# STLink_V3E_Module.net
KiCad netlist of a schematic drawn in Altium Designer
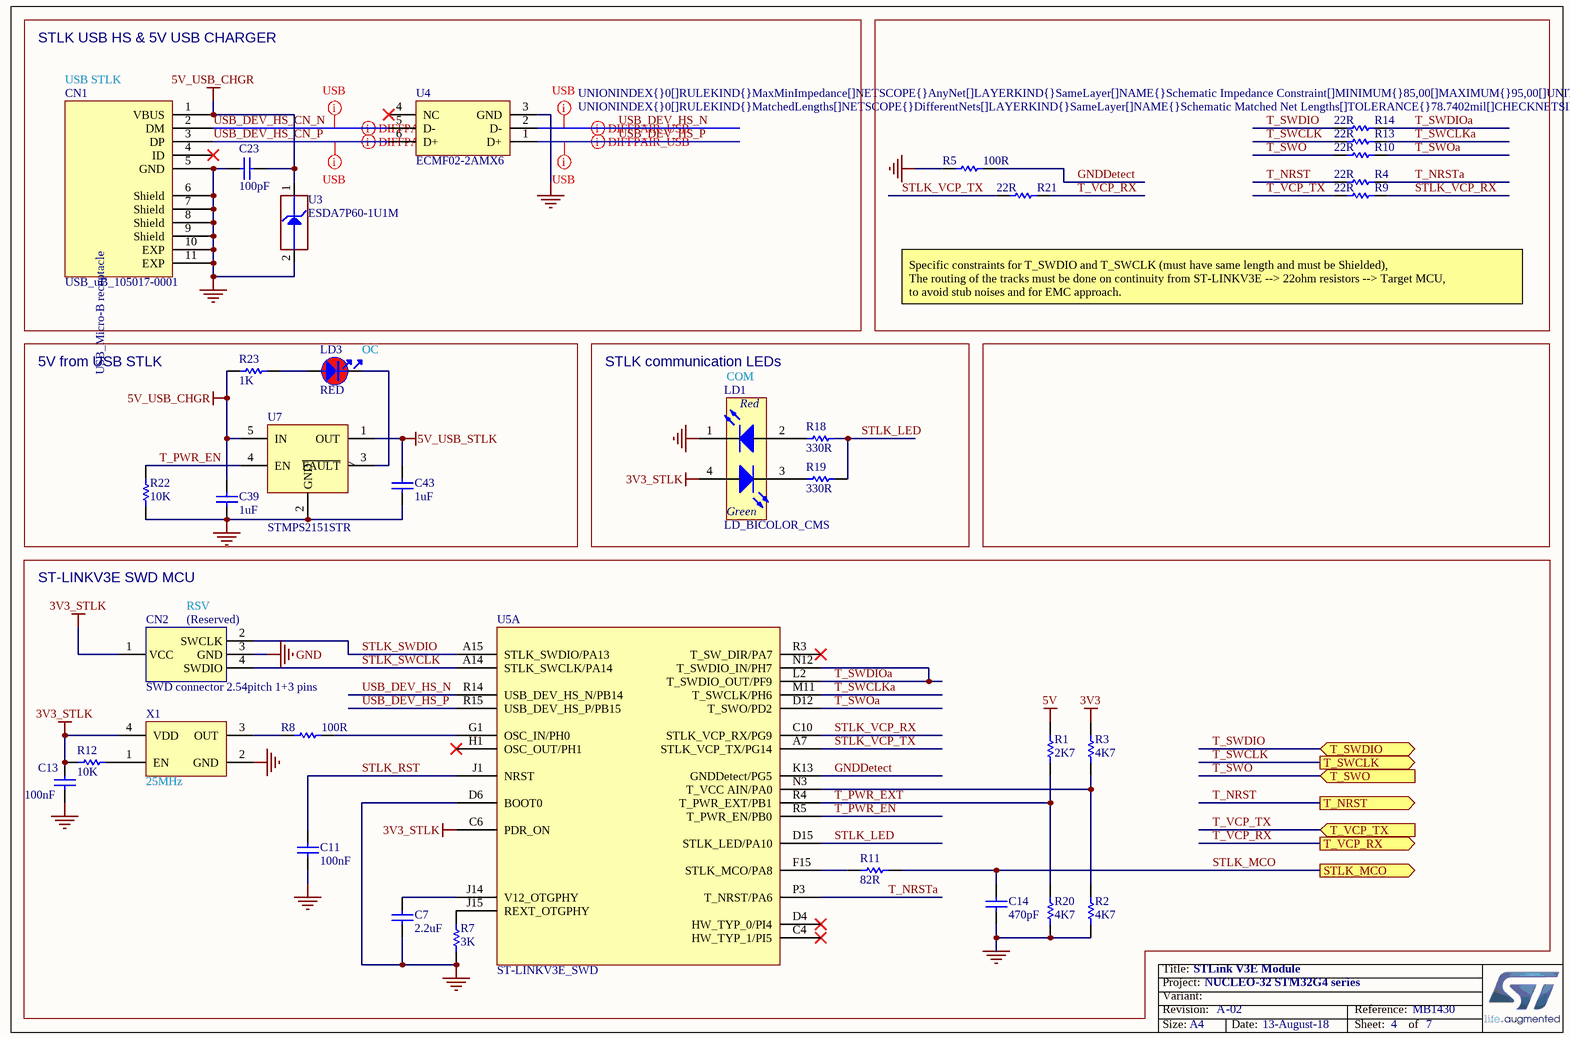
[diagram p0: STLink_V3E_Module.SchDoc]

(export (version "E")
  (design (tool "Eeschema 10.0.6"))
  (components
    (comp (ref "C7")
      (value "2.2uF")
      (footprint "C0603")
      (description "Capacitor, MLCC, 2.2uF, 10V, X5R, 10%, 0603, T=0,8mm")
      (fields
        (field (name "INTERNAL_PART_NUMBER") "MCD-00012")
        (field (name "MANUFACTURER_PART_NUMBER") "CC0603KRX5R6BB225")
        (field (name "PROVIDED_BY") "SUBCO")
      )
      (libsource (lib "MCD_PARTS_database") (part "Capacitor"))
    )
    (comp (ref "C11")
      (value "100nF")
      (footprint "C0402")
      (description "Capacitor, MLCC, 100nF, 16V, X7R, 10%, 0402, T=0,5mm")
      (fields
        (field (name "INTERNAL_PART_NUMBER") "MCD-00102")
        (field (name "MANUFACTURER_PART_NUMBER") "CC0402KRX7R7BB104")
        (field (name "PROVIDED_BY") "SUBCO")
      )
      (libsource (lib "MCD_PARTS_database") (part "Capacitor"))
    )
    (comp (ref "C13")
      (value "100nF")
      (footprint "C0402")
      (description "Capacitor, MLCC, 100nF, 16V, X7R, 10%, 0402, T=0,5mm")
      (fields
        (field (name "INTERNAL_PART_NUMBER") "MCD-00102")
        (field (name "MANUFACTURER_PART_NUMBER") "CC0402KRX7R7BB104")
        (field (name "PROVIDED_BY") "SUBCO")
      )
      (libsource (lib "MCD_PARTS_database") (part "Capacitor"))
    )
    (comp (ref "C14")
      (value "470pF")
      (footprint "C0402")
      (description "Capacitor, MLCC, 470pF, 50V, NPO, 5%, 0402, T=0,5mm")
      (fields
        (field (name "INTERNAL_PART_NUMBER") "MCD-00724")
        (field (name "MANUFACTURER_PART_NUMBER") "CC0402JRNPO9BN471")
        (field (name "PROVIDED_BY") "SUBCO")
      )
      (libsource (lib "MCD_PARTS_database") (part "Capacitor"))
    )
    (comp (ref "C23")
      (value "100pF")
      (footprint "C0402")
      (description "Capacitor, MLCC, 100pF, 50V, NPO, 5%, 0402, T=0,5mm")
      (fields
        (field (name "INTERNAL_PART_NUMBER") "MCD-00205")
        (field (name "MANUFACTURER_PART_NUMBER") "CC0402JRNPO9BN101")
        (field (name "PROVIDED_BY") "SUBCO")
      )
      (libsource (lib "MCD_PARTS_database") (part "Capacitor"))
    )
    (comp (ref "C39")
      (value "1uF")
      (footprint "C0603")
      (description "Capacitor, MLCC, 1uF, 16V, X5R, 10%, 0603, T=0,8mm")
      (fields
        (field (name "INTERNAL_PART_NUMBER") "MCD-00010")
        (field (name "MANUFACTURER_PART_NUMBER") "CC0603KRX5R7BB105")
        (field (name "PROVIDED_BY") "SUBCO")
      )
      (libsource (lib "MCD_PARTS_database") (part "Capacitor"))
    )
    (comp (ref "C43")
      (value "1uF")
      (footprint "C0603")
      (description "Capacitor, MLCC, 1uF, 16V, X5R, 10%, 0603, T=0,8mm")
      (fields
        (field (name "INTERNAL_PART_NUMBER") "MCD-00010")
        (field (name "MANUFACTURER_PART_NUMBER") "CC0603KRX5R7BB105")
        (field (name "PROVIDED_BY") "SUBCO")
      )
      (libsource (lib "MCD_PARTS_database") (part "Capacitor"))
    )
    (comp (ref "CN1")
      (value "USB_uB_105017-0001")
      (footprint "CON_USBMICROB_MOLEX_105017-0001_H2P90")
      (description "USB-MICRO-B, 0.65mm, RA, SMT, Bottom Mount,")
      (fields
        (field (name "INTERNAL_PART_NUMBER") "MCD-00028")
        (field (name "MANUFACTURER_PART_NUMBER") "1050170001")
        (field (name "PROVIDED_BY") "SUBCO")
      )
      (libsource (lib "MCD_PARTS_database") (part "USB_uB_105017.0001"))
    )
    (comp (ref "CN2")
      (value "SWD connector 2.54pitch 1+3 pins")
      (footprint "CON_SAMTEC_TSW-103-07-X-D_CUSTOM_4PINS__V1-3")
      (description "SWD connector 2.54pitch 1+3 pins - not fitted")
      (fields
        (field (name "INTERNAL_PART_NUMBER") "MCD-01430")
        (field (name "MANUFACTURER_PART_NUMBER") "na")
      )
      (libsource (lib "MCD_PARTS_database") (part "SWD_CN_1+3"))
    )
    (comp (ref "LD1")
      (value "LD_BICOLOR_CMS")
      (footprint "LED_BI-GR_HSMF-A201-A00J1")
      (description "LED Bicolor")
      (fields
        (field (name "INTERNAL_PART_NUMBER") "MCD-00051")
        (field (name "MANUFACTURER_PART_NUMBER") "HSMF-A201-A00J1")
        (field (name "PROVIDED_BY") "SUBCO")
      )
      (libsource (lib "MCD_PARTS_database") (part "LD_BICOLOR_CMS"))
    )
    (comp (ref "LD3")
      (value "RED")
      (footprint "LED_0603_RED_H0P4")
      (description "LED, Red, 0603")
      (fields
        (field (name "INTERNAL_PART_NUMBER") "MCD-00322")
        (field (name "MANUFACTURER_PART_NUMBER") "19-217/R6C-AL1M2VY/3T")
        (field (name "PROVIDED_BY") "SUBCO")
      )
      (libsource (lib "MCD_PARTS_database") (part "LED_red"))
    )
    (comp (ref "R1")
      (value "2K7")
      (footprint "R0402")
      (description "Resistor,2K7,0402,1%,1/16W")
      (fields
        (field (name "INTERNAL_PART_NUMBER") "MCD-00055")
        (field (name "MANUFACTURER_PART_NUMBER") "RC0402FR-072K7L")
        (field (name "PROVIDED_BY") "SUBCO")
      )
      (libsource (lib "MCD_PARTS_database") (part "Resistor"))
    )
    (comp (ref "R2")
      (value "4K7")
      (footprint "R0402")
      (description "Resistor,4K7,0402,1%,1/16W")
      (fields
        (field (name "INTERNAL_PART_NUMBER") "MCD-00065")
        (field (name "MANUFACTURER_PART_NUMBER") "RC0402FR-074K7L")
        (field (name "PROVIDED_BY") "SUBCO")
      )
      (libsource (lib "MCD_PARTS_database") (part "Resistor"))
    )
    (comp (ref "R3")
      (value "4K7")
      (footprint "R0402")
      (description "Resistor,4K7,0402,1%,1/16W")
      (fields
        (field (name "INTERNAL_PART_NUMBER") "MCD-00065")
        (field (name "MANUFACTURER_PART_NUMBER") "RC0402FR-074K7L")
        (field (name "PROVIDED_BY") "SUBCO")
      )
      (libsource (lib "MCD_PARTS_database") (part "Resistor"))
    )
    (comp (ref "R4")
      (value "22R")
      (footprint "R0402")
      (description "Resistor,22R,0402,1%,1/16W")
      (fields
        (field (name "INTERNAL_PART_NUMBER") "MCD-00189")
        (field (name "MANUFACTURER_PART_NUMBER") "RC0402FR-0722RL")
        (field (name "PROVIDED_BY") "SUBCO")
      )
      (libsource (lib "MCD_PARTS_database") (part "Resistor"))
    )
    (comp (ref "R5")
      (value "100R")
      (footprint "R0402")
      (description "Resistor,100R,0402,1%,1/16W")
      (fields
        (field (name "INTERNAL_PART_NUMBER") "MCD-00119")
        (field (name "MANUFACTURER_PART_NUMBER") "RC0402FR-07100RL")
        (field (name "PROVIDED_BY") "SUBCO")
      )
      (libsource (lib "MCD_PARTS_database") (part "Resistor"))
    )
    (comp (ref "R7")
      (value "3K")
      (footprint "R0402")
      (description "Resistor,3K,0402,1%,1/16W")
      (fields
        (field (name "INTERNAL_PART_NUMBER") "MCD-00185")
        (field (name "MANUFACTURER_PART_NUMBER") "RC0402FR-073KL")
        (field (name "PROVIDED_BY") "SUBCO")
      )
      (libsource (lib "MCD_PARTS_database") (part "Resistor"))
    )
    (comp (ref "R8")
      (value "100R")
      (footprint "R0402")
      (description "Resistor,100R,0402,1%,1/16W")
      (fields
        (field (name "INTERNAL_PART_NUMBER") "MCD-00119")
        (field (name "MANUFACTURER_PART_NUMBER") "RC0402FR-07100RL")
        (field (name "PROVIDED_BY") "SUBCO")
      )
      (libsource (lib "MCD_PARTS_database") (part "Resistor"))
    )
    (comp (ref "R9")
      (value "22R")
      (footprint "R0402")
      (description "Resistor,22R,0402,1%,1/16W")
      (fields
        (field (name "INTERNAL_PART_NUMBER") "MCD-00189")
        (field (name "MANUFACTURER_PART_NUMBER") "RC0402FR-0722RL")
        (field (name "PROVIDED_BY") "SUBCO")
      )
      (libsource (lib "MCD_PARTS_database") (part "Resistor"))
    )
    (comp (ref "R10")
      (value "22R")
      (footprint "R0402")
      (description "Resistor,22R,0402,1%,1/16W")
      (fields
        (field (name "INTERNAL_PART_NUMBER") "MCD-00189")
        (field (name "MANUFACTURER_PART_NUMBER") "RC0402FR-0722RL")
        (field (name "PROVIDED_BY") "SUBCO")
      )
      (libsource (lib "MCD_PARTS_database") (part "Resistor"))
    )
    (comp (ref "R11")
      (value "82R")
      (footprint "R0402")
      (description "Resistor,82R,0402,1%,1/16W")
      (fields
        (field (name "INTERNAL_PART_NUMBER") "MCD-00525")
        (field (name "MANUFACTURER_PART_NUMBER") "RC0402FR-0782RL")
        (field (name "PROVIDED_BY") "SUBCO")
      )
      (libsource (lib "MCD_PARTS_database") (part "Resistor"))
    )
    (comp (ref "R12")
      (value "10K")
      (footprint "R0402")
      (description "Resistor,10K,0402,1%,1/16W")
      (fields
        (field (name "INTERNAL_PART_NUMBER") "MCD-00053")
        (field (name "MANUFACTURER_PART_NUMBER") "RC0402FR-0710KL")
        (field (name "PROVIDED_BY") "SUBCO")
      )
      (libsource (lib "MCD_PARTS_database") (part "Resistor"))
    )
    (comp (ref "R13")
      (value "22R")
      (footprint "R0402")
      (description "Resistor,22R,0402,1%,1/16W")
      (fields
        (field (name "INTERNAL_PART_NUMBER") "MCD-00189")
        (field (name "MANUFACTURER_PART_NUMBER") "RC0402FR-0722RL")
        (field (name "PROVIDED_BY") "SUBCO")
      )
      (libsource (lib "MCD_PARTS_database") (part "Resistor"))
    )
    (comp (ref "R14")
      (value "22R")
      (footprint "R0402")
      (description "Resistor,22R,0402,1%,1/16W")
      (fields
        (field (name "INTERNAL_PART_NUMBER") "MCD-00189")
        (field (name "MANUFACTURER_PART_NUMBER") "RC0402FR-0722RL")
        (field (name "PROVIDED_BY") "SUBCO")
      )
      (libsource (lib "MCD_PARTS_database") (part "Resistor"))
    )
    (comp (ref "R18")
      (value "330R")
      (footprint "R0603")
      (description "Resistor,330R,0603,1%,1/10W")
      (fields
        (field (name "INTERNAL_PART_NUMBER") "MCD-00197")
        (field (name "MANUFACTURER_PART_NUMBER") "RC0603FR-07330RL")
        (field (name "PROVIDED_BY") "SUBCO")
      )
      (libsource (lib "MCD_PARTS_database") (part "Resistor"))
    )
    (comp (ref "R19")
      (value "330R")
      (footprint "R0603")
      (description "Resistor,330R,0603,1%,1/10W")
      (fields
        (field (name "INTERNAL_PART_NUMBER") "MCD-00197")
        (field (name "MANUFACTURER_PART_NUMBER") "RC0603FR-07330RL")
        (field (name "PROVIDED_BY") "SUBCO")
      )
      (libsource (lib "MCD_PARTS_database") (part "Resistor"))
    )
    (comp (ref "R20")
      (value "4K7")
      (footprint "R0402")
      (description "Resistor,4K7,0402,1%,1/16W")
      (fields
        (field (name "INTERNAL_PART_NUMBER") "MCD-00065")
        (field (name "MANUFACTURER_PART_NUMBER") "RC0402FR-074K7L")
        (field (name "PROVIDED_BY") "SUBCO")
      )
      (libsource (lib "MCD_PARTS_database") (part "Resistor"))
    )
    (comp (ref "R21")
      (value "22R")
      (footprint "R0402")
      (description "Resistor,22R,0402,1%,1/16W")
      (fields
        (field (name "INTERNAL_PART_NUMBER") "MCD-00189")
        (field (name "MANUFACTURER_PART_NUMBER") "RC0402FR-0722RL")
        (field (name "PROVIDED_BY") "SUBCO")
      )
      (libsource (lib "MCD_PARTS_database") (part "Resistor"))
    )
    (comp (ref "R22")
      (value "10K")
      (footprint "R0402")
      (description "Resistor,10K,0402,1%,1/16W")
      (fields
        (field (name "INTERNAL_PART_NUMBER") "MCD-00053")
        (field (name "MANUFACTURER_PART_NUMBER") "RC0402FR-0710KL")
        (field (name "PROVIDED_BY") "SUBCO")
      )
      (libsource (lib "MCD_PARTS_database") (part "Resistor"))
    )
    (comp (ref "R23")
      (value "1K")
      (footprint "R0603")
      (description "Resistor,1K,0603,1%,1/10W")
      (fields
        (field (name "INTERNAL_PART_NUMBER") "MCD-00070")
        (field (name "MANUFACTURER_PART_NUMBER") "RC0603FR-071KL")
        (field (name "PROVIDED_BY") "SUBCO")
      )
      (libsource (lib "MCD_PARTS_database") (part "Resistor"))
    )
    (comp (ref "U3")
      (value "ESDA7P60-1U1M")
      (footprint "ESD_QFN2_1P6X1_P125")
      (description "High power transient voltage suppressor, 7V breakdown")
      (fields
        (field (name "INTERNAL_PART_NUMBER") "MCD-00251")
        (field (name "MANUFACTURER") "STMICROELECTRONICS")
        (field (name "PROVIDED_BY") "SUBCO with ST control")
      )
      (libsource (lib "MCD_PARTS_database") (part "ESD-TRANSIL"))
    )
    (comp (ref "U4")
      (value "ECMF02-2AMX6")
      (footprint "ESD_QFN-6L_1P7X1P5_P050")
      (description "Common mode filter with ESD protection for USB 2.0 interface")
      (fields
        (field (name "INTERNAL_PART_NUMBER") "MCD-00649")
        (field (name "MANUFACTURER") "STMICROELECTRONICS")
        (field (name "PROVIDED_BY") "SUBCO with ST control")
      )
      (libsource (lib "MCD_PARTS_database") (part "ECMF02-2AMX6"))
    )
    (comp (ref "U5")
      (value "ST-LINKV3E_SWD")
      (footprint "ICC_UFBGA201_176+25_10X10_P065")
      (description "STM32F723IEK  (STM32F7) BGA176")
      (fields
        (field (name "INTERNAL_PART_NUMBER") "MCD-00596")
        (field (name "MANUFACTURER_PART_NUMBER") "STM32F723IEK6")
        (field (name "PROVIDED_BY") "SUBCO with ST control")
      )
      (libsource (lib "MCD_PARTS_database") (part "ST-LINKV3E_SWD"))
    )
    (comp (ref "U7")
      (value "STMPS2151STR")
      (footprint "MOS_SOT23-5L")
      (description "500mA, Enhanced single channel power switches with active high enable pin")
      (fields
        (field (name "INTERNAL_PART_NUMBER") "MCD-00159")
        (field (name "MANUFACTURER") "STMICROELECTRONICS")
        (field (name "PROVIDED_BY") "SUBCO with ST control")
      )
      (libsource (lib "MCD_PARTS_database") (part "STMPS2151STR"))
    )
    (comp (ref "X1")
      (value "25MHz")
      (footprint "OSC_NDK_NZ2520SB_4P")
      (description "Oscillator 25.00Mhz, -+50PPM, 3.3V, Temp -55 to +125°C")
      (fields
        (field (name "INTERNAL_PART_NUMBER") "MCD-00597")
        (field (name "MANUFACTURER_PART_NUMBER") "NZ2520SB 25MHz END4869B")
      )
      (libsource (lib "MCD_PARTS_database") (part "OSCILLATOR_4_PINS"))
    )
  )
  (nets
    (net (code "1") (name "/GNDDetect") (class "Default")
      (node (ref "R5") (pin "2") (pinfunction "2_2") (pintype "passive"))
      (node (ref "U5") (pin "K13") (pinfunction "GNDDetect/PG5_K13") (pintype "passive"))
    )
    (net (code "2") (name "/STLK_LED") (class "Default")
      (node (ref "R18") (pin "2") (pinfunction "2_2") (pintype "passive"))
      (node (ref "R19") (pin "2") (pinfunction "2_2") (pintype "passive"))
      (node (ref "U5") (pin "D15") (pinfunction "STLK_LED/PA10_D15") (pintype "passive"))
    )
    (net (code "3") (name "/STLK_MCO") (class "Default")
      (node (ref "C14") (pin "2") (pinfunction "2_2") (pintype "passive"))
      (node (ref "R11") (pin "2") (pinfunction "2_2") (pintype "passive"))
    )
    (net (code "4") (name "/STLK_RST") (class "Default")
      (node (ref "C11") (pin "2") (pinfunction "2_2") (pintype "passive"))
      (node (ref "U5") (pin "J1") (pinfunction "NRST_J1") (pintype "passive"))
    )
    (net (code "5") (name "/STLK_SWCLK") (class "Default")
      (node (ref "CN2") (pin "4") (pinfunction "SWDIO_4") (pintype "passive"))
      (node (ref "U5") (pin "A14") (pinfunction "STLK_SWCLK/PA14_A14") (pintype "passive"))
    )
    (net (code "6") (name "/STLK_SWDIO") (class "Default")
      (node (ref "CN2") (pin "2") (pinfunction "SWCLK_2") (pintype "passive"))
      (node (ref "U5") (pin "A15") (pinfunction "STLK_SWDIO/PA13_A15") (pintype "passive"))
    )
    (net (code "7") (name "/STLK_VCP_RX") (class "Default")
      (node (ref "R9") (pin "2") (pinfunction "2_2") (pintype "passive"))
      (node (ref "U5") (pin "C10") (pinfunction "STLK_VCP_RX/PG9_C10") (pintype "passive"))
    )
    (net (code "8") (name "/STLK_VCP_TX") (class "Default")
      (node (ref "R21") (pin "1") (pinfunction "1_1") (pintype "passive"))
      (node (ref "U5") (pin "A7") (pinfunction "STLK_VCP_TX/PG14_A7") (pintype "passive"))
    )
    (net (code "9") (name "/T_NRST") (class "Default")
      (node (ref "R4") (pin "1") (pinfunction "1_1") (pintype "passive"))
    )
    (net (code "10") (name "/T_NRSTa") (class "Default")
      (node (ref "R4") (pin "2") (pinfunction "2_2") (pintype "passive"))
      (node (ref "U5") (pin "P3") (pinfunction "T_NRST/PA6_P3") (pintype "passive"))
    )
    (net (code "11") (name "/T_PWR_EN") (class "Default")
      (node (ref "R22") (pin "2") (pinfunction "2_2") (pintype "passive"))
      (node (ref "U5") (pin "R5") (pinfunction "T_PWR_EN/PB0_R5") (pintype "passive"))
      (node (ref "U7") (pin "4") (pinfunction "EN_4") (pintype "passive"))
    )
    (net (code "12") (name "/T_PWR_EXT") (class "Default")
      (node (ref "R1") (pin "1") (pinfunction "1_1") (pintype "passive"))
      (node (ref "R20") (pin "2") (pinfunction "2_2") (pintype "passive"))
      (node (ref "U5") (pin "R4") (pinfunction "T_PWR_EXT/PB1_R4") (pintype "passive"))
    )
    (net (code "13") (name "/T_SWCLK") (class "Default")
      (node (ref "R13") (pin "1") (pinfunction "1_1") (pintype "passive"))
    )
    (net (code "14") (name "/T_SWCLKa") (class "Default")
      (node (ref "R13") (pin "2") (pinfunction "2_2") (pintype "passive"))
      (node (ref "U5") (pin "M11") (pinfunction "T_SWCLK/PH6_M11") (pintype "passive"))
    )
    (net (code "15") (name "/T_SWDIO") (class "Default")
      (node (ref "R14") (pin "1") (pinfunction "1_1") (pintype "passive"))
    )
    (net (code "16") (name "/T_SWDIOa") (class "Default")
      (node (ref "R14") (pin "2") (pinfunction "2_2") (pintype "passive"))
      (node (ref "U5") (pin "L2") (pinfunction "T_SWDIO_OUT/PF9_L2") (pintype "passive"))
      (node (ref "U5") (pin "N12") (pinfunction "T_SWDIO_IN/PH7_N12") (pintype "passive"))
    )
    (net (code "17") (name "/T_SWO") (class "Default")
      (node (ref "R10") (pin "1") (pinfunction "1_1") (pintype "passive"))
    )
    (net (code "18") (name "/T_SWOa") (class "Default")
      (node (ref "R10") (pin "2") (pinfunction "2_2") (pintype "passive"))
      (node (ref "U5") (pin "D12") (pinfunction "T_SWO/PD2_D12") (pintype "passive"))
    )
    (net (code "19") (name "/T_VCP_RX") (class "Default")
      (node (ref "R21") (pin "2") (pinfunction "2_2") (pintype "passive"))
    )
    (net (code "20") (name "/T_VCP_TX") (class "Default")
      (node (ref "R9") (pin "1") (pinfunction "1_1") (pintype "passive"))
    )
    (net (code "21") (name "/USB_DEV_HS_CN_N") (class "Default")
      (node (ref "CN1") (pin "2") (pinfunction "DM_2") (pintype "passive"))
      (node (ref "U4") (pin "5") (pinfunction "D-_5") (pintype "passive"))
    )
    (net (code "22") (name "/USB_DEV_HS_CN_P") (class "Default")
      (node (ref "CN1") (pin "3") (pinfunction "DP_3") (pintype "passive"))
      (node (ref "U4") (pin "6") (pinfunction "D+_6") (pintype "passive"))
    )
    (net (code "23") (name "/USB_DEV_HS_N") (class "Default")
      (node (ref "U4") (pin "2") (pinfunction "D-_2") (pintype "passive"))
      (node (ref "U5") (pin "R14") (pinfunction "USB_DEV_HS_N/PB14_R14") (pintype "passive"))
    )
    (net (code "24") (name "/USB_DEV_HS_P") (class "Default")
      (node (ref "U4") (pin "1") (pinfunction "D+_1") (pintype "passive"))
      (node (ref "U5") (pin "R15") (pinfunction "USB_DEV_HS_P/PB15_R15") (pintype "passive"))
    )
    (net (code "25") (name "3V3") (class "Default")
      (node (ref "R3") (pin "2") (pinfunction "2_2") (pintype "passive"))
    )
    (net (code "26") (name "3V3_STLK") (class "Default")
      (node (ref "C13") (pin "2") (pinfunction "2_2") (pintype "passive"))
      (node (ref "CN2") (pin "1") (pinfunction "VCC_1") (pintype "passive"))
      (node (ref "LD1") (pin "4") (pinfunction "YellowGreen_anode_4") (pintype "passive"))
      (node (ref "R12") (pin "1") (pinfunction "1_1") (pintype "passive"))
      (node (ref "U5") (pin "C6") (pinfunction "PDR_ON_C6") (pintype "passive"))
      (node (ref "X1") (pin "4") (pinfunction "VDD_4") (pintype "passive"))
    )
    (net (code "27") (name "5V") (class "Default")
      (node (ref "R1") (pin "2") (pinfunction "2_2") (pintype "passive"))
    )
    (net (code "28") (name "5V_USB_CHGR") (class "Default")
      (node (ref "C23") (pin "2") (pinfunction "2_2") (pintype "passive"))
      (node (ref "C39") (pin "2") (pinfunction "2_2") (pintype "passive"))
      (node (ref "CN1") (pin "1") (pinfunction "VBUS_1") (pintype "passive"))
      (node (ref "R23") (pin "1") (pinfunction "1_1") (pintype "passive"))
      (node (ref "U3") (pin "1") (pinfunction "IO1_1") (pintype "passive"))
      (node (ref "U7") (pin "5") (pinfunction "IN_5") (pintype "passive"))
    )
    (net (code "29") (name "5V_USB_STLK") (class "Default")
      (node (ref "C43") (pin "2") (pinfunction "2_2") (pintype "passive"))
      (node (ref "U7") (pin "1") (pinfunction "OUT_1") (pintype "passive"))
    )
    (net (code "30") (name "GND") (class "Default")
      (node (ref "C11") (pin "1") (pinfunction "1_1") (pintype "passive"))
      (node (ref "C13") (pin "1") (pinfunction "1_1") (pintype "passive"))
      (node (ref "C14") (pin "1") (pinfunction "1_1") (pintype "passive"))
      (node (ref "C23") (pin "1") (pinfunction "1_1") (pintype "passive"))
      (node (ref "C39") (pin "1") (pinfunction "1_1") (pintype "passive"))
      (node (ref "C43") (pin "1") (pinfunction "1_1") (pintype "passive"))
      (node (ref "C7") (pin "1") (pinfunction "1_1") (pintype "passive"))
      (node (ref "CN1") (pin "10") (pinfunction "EXP_10") (pintype "passive"))
      (node (ref "CN1") (pin "11") (pinfunction "EXP_11") (pintype "passive"))
      (node (ref "CN1") (pin "5") (pinfunction "GND_5") (pintype "passive"))
      (node (ref "CN1") (pin "6") (pinfunction "Shield_6") (pintype "passive"))
      (node (ref "CN1") (pin "7") (pinfunction "Shield_7") (pintype "passive"))
      (node (ref "CN1") (pin "8") (pinfunction "Shield_8") (pintype "passive"))
      (node (ref "CN1") (pin "9") (pinfunction "Shield_9") (pintype "passive"))
      (node (ref "CN2") (pin "3") (pinfunction "GND_3") (pintype "passive"))
      (node (ref "LD1") (pin "1") (pinfunction "RED_cathode_1") (pintype "passive"))
      (node (ref "R2") (pin "1") (pinfunction "1_1") (pintype "passive"))
      (node (ref "R20") (pin "1") (pinfunction "1_1") (pintype "passive"))
      (node (ref "R22") (pin "1") (pinfunction "1_1") (pintype "passive"))
      (node (ref "R5") (pin "1") (pinfunction "1_1") (pintype "passive"))
      (node (ref "R7") (pin "1") (pinfunction "1_1") (pintype "passive"))
      (node (ref "U3") (pin "2") (pinfunction "GND_2") (pintype "passive"))
      (node (ref "U4") (pin "3") (pinfunction "GND_3") (pintype "passive"))
      (node (ref "U5") (pin "D6") (pinfunction "BOOT0_D6") (pintype "passive"))
      (node (ref "U7") (pin "2") (pinfunction "GND_2") (pintype "passive"))
      (node (ref "X1") (pin "2") (pinfunction "GND_2") (pintype "passive"))
    )
    (net (code "31") (name "Net-(LD1-Red_anode)") (class "Default")
      (node (ref "LD1") (pin "2") (pinfunction "Red_anode_2") (pintype "passive"))
      (node (ref "R18") (pin "1") (pinfunction "1_1") (pintype "passive"))
    )
    (net (code "32") (name "Net-(LD1-YellowGreen_cathode)") (class "Default")
      (node (ref "LD1") (pin "3") (pinfunction "YellowGreen_cathode_3") (pintype "passive"))
      (node (ref "R19") (pin "1") (pinfunction "1_1") (pintype "passive"))
    )
    (net (code "33") (name "Net-(LD3-Pad1)") (class "Default")
      (node (ref "LD3") (pin "1") (pintype "passive"))
      (node (ref "R23") (pin "2") (pinfunction "2_2") (pintype "passive"))
    )
    (net (code "34") (name "Net-(U5A-OSC_IN{slash}PH0)") (class "Default")
      (node (ref "R8") (pin "2") (pinfunction "2_2") (pintype "passive"))
      (node (ref "U5") (pin "G1") (pinfunction "OSC_IN/PH0_G1") (pintype "passive"))
    )
    (net (code "35") (name "Net-(U5A-REXT_OTGPHY)") (class "Default")
      (node (ref "R7") (pin "2") (pinfunction "2_2") (pintype "passive"))
      (node (ref "U5") (pin "J15") (pinfunction "REXT_OTGPHY_J15") (pintype "passive"))
    )
    (net (code "36") (name "Net-(U5A-STLK_MCO{slash}PA8)") (class "Default")
      (node (ref "R11") (pin "1") (pinfunction "1_1") (pintype "passive"))
      (node (ref "U5") (pin "F15") (pinfunction "STLK_MCO/PA8_F15") (pintype "passive"))
    )
    (net (code "37") (name "Net-(U5A-T_VCC_AIN{slash}PA0)") (class "Default")
      (node (ref "R2") (pin "2") (pinfunction "2_2") (pintype "passive"))
      (node (ref "R3") (pin "1") (pinfunction "1_1") (pintype "passive"))
      (node (ref "U5") (pin "N3") (pinfunction "T_VCC_AIN/PA0_N3") (pintype "passive"))
    )
    (net (code "38") (name "Net-(U5A-V12_OTGPHY)") (class "Default")
      (node (ref "C7") (pin "2") (pinfunction "2_2") (pintype "passive"))
      (node (ref "U5") (pin "J14") (pinfunction "V12_OTGPHY_J14") (pintype "passive"))
    )
    (net (code "39") (name "Net-(U7-~{FAULT})") (class "Default")
      (node (ref "LD3") (pin "2") (pintype "passive"))
      (node (ref "U7") (pin "3") (pinfunction "~{FAULT}_3") (pintype "passive"))
    )
    (net (code "40") (name "Net-(X1-EN)") (class "Default")
      (node (ref "R12") (pin "2") (pinfunction "2_2") (pintype "passive"))
      (node (ref "X1") (pin "1") (pinfunction "EN_1") (pintype "passive"))
    )
    (net (code "41") (name "Net-(X1-OUT)") (class "Default")
      (node (ref "R8") (pin "1") (pinfunction "1_1") (pintype "passive"))
      (node (ref "X1") (pin "3") (pinfunction "OUT_3") (pintype "passive"))
    )
    (net (code "42") (name "unconnected-(CN1-ID-Pad4)") (class "Default")
      (node (ref "CN1") (pin "4") (pinfunction "ID_4") (pintype "passive+no_connect"))
    )
    (net (code "43") (name "unconnected-(U4-NC-Pad4)") (class "Default")
      (node (ref "U4") (pin "4") (pinfunction "NC_4") (pintype "passive+no_connect"))
    )
    (net (code "44") (name "unconnected-(U5A-HW_TYP_0{slash}PI4-PadD4)") (class "Default")
      (node (ref "U5") (pin "D4") (pinfunction "HW_TYP_0/PI4_D4") (pintype "passive+no_connect"))
    )
    (net (code "45") (name "unconnected-(U5A-HW_TYP_1{slash}PI5-PadC4)") (class "Default")
      (node (ref "U5") (pin "C4") (pinfunction "HW_TYP_1/PI5_C4") (pintype "passive+no_connect"))
    )
    (net (code "46") (name "unconnected-(U5A-OSC_OUT{slash}PH1-PadH1)") (class "Default")
      (node (ref "U5") (pin "H1") (pinfunction "OSC_OUT/PH1_H1") (pintype "passive+no_connect"))
    )
    (net (code "47") (name "unconnected-(U5A-T_SW_DIR{slash}PA7-PadR3)") (class "Default")
      (node (ref "U5") (pin "R3") (pinfunction "T_SW_DIR/PA7_R3") (pintype "passive+no_connect"))
    )
  )
)
